# controllerver2.net
KiCad netlist of a schematic drawn in EAGLE
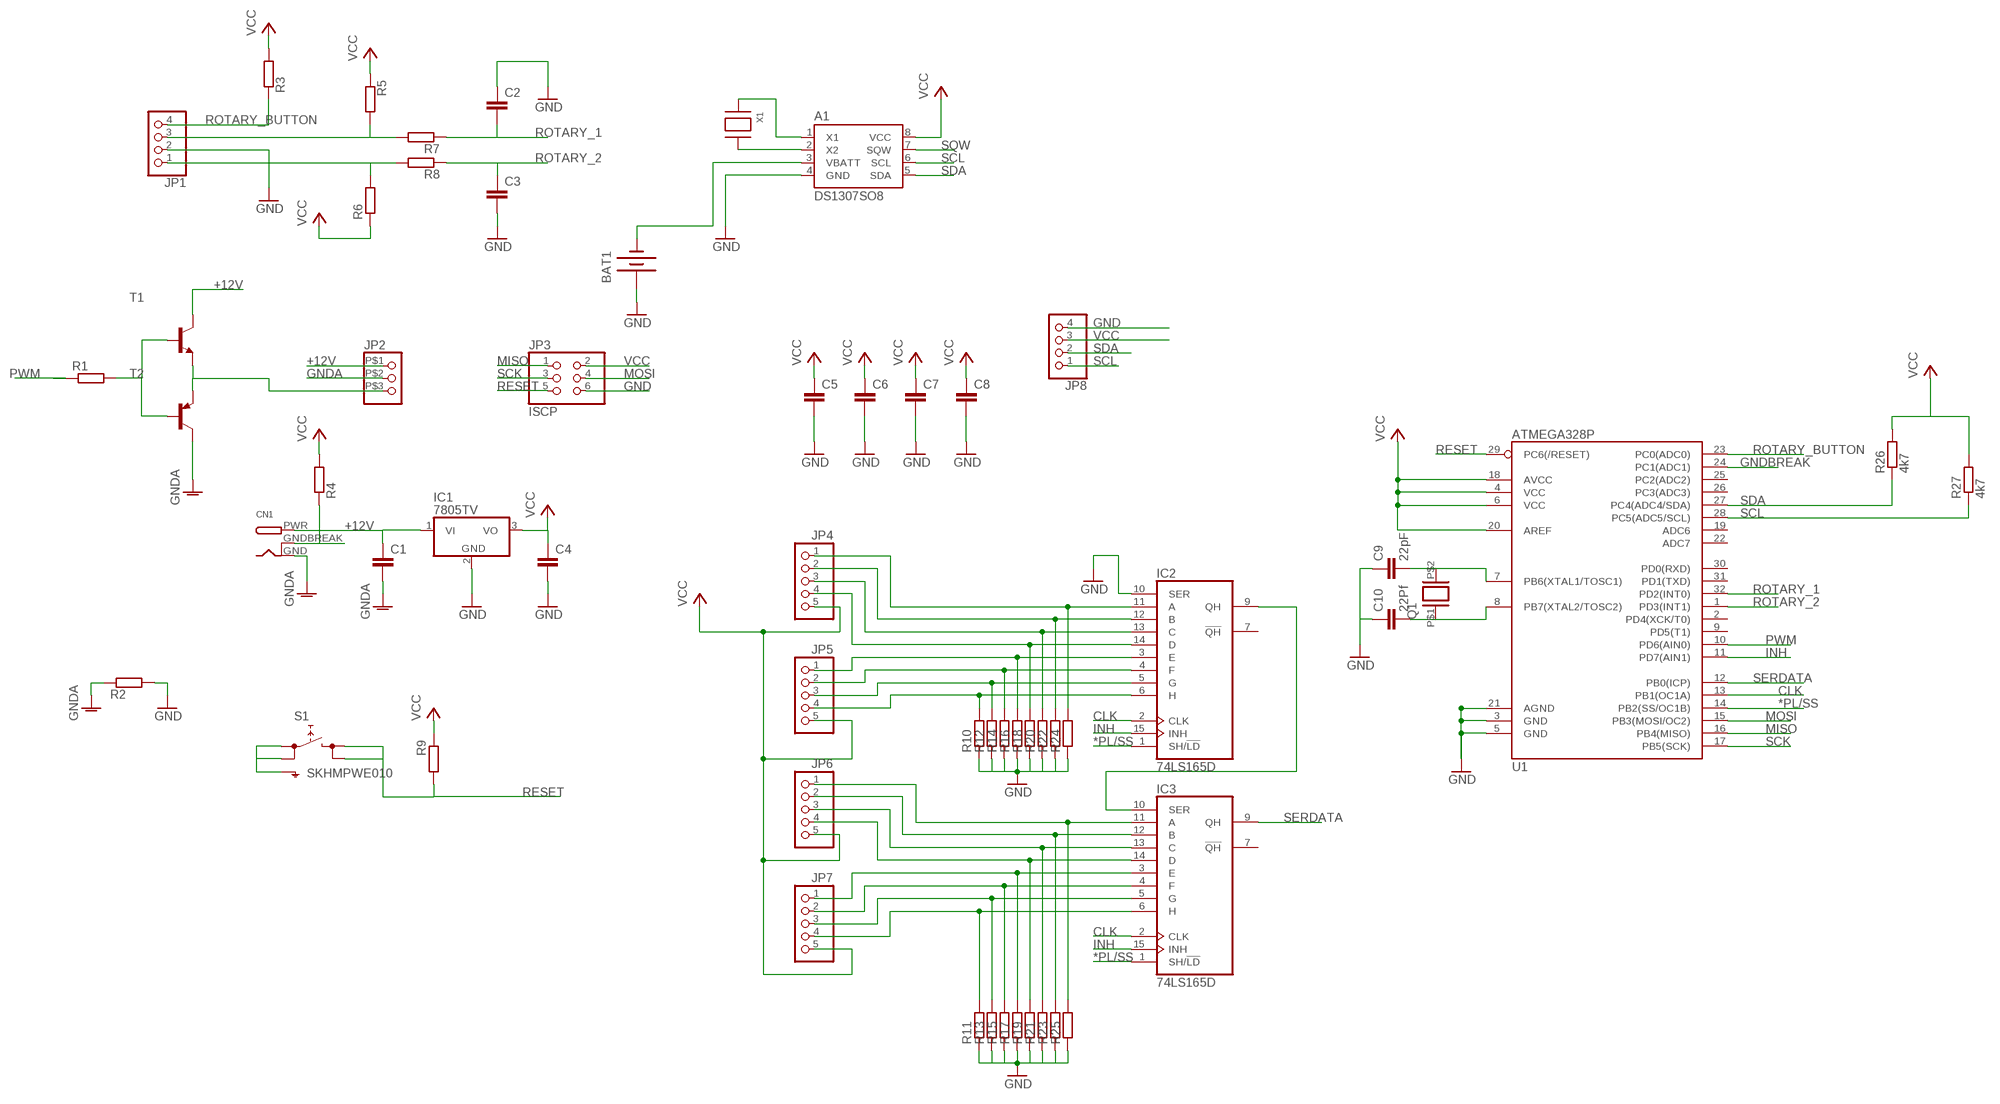
[diagram p0: schematic, sheet 1]

(export (version "E")
  (design (tool "Eeschema 10.0.6"))
  (components
    (comp (ref "A1")
      (value "DS1307SO8")
      (footprint "eagle-import:SO08")
      (libsource (lib "eagle-import") (part "DS1307SO8"))
    )
    (comp (ref "BAT1")
      (value "BATTERY20SMD")
      (footprint "eagle-import:BATTCON_20MM")
      (libsource (lib "eagle-import") (part "BATTERY20SMD"))
    )
    (comp (ref "C1")
      (value "C-EUC0805")
      (footprint "eagle-import:C0805")
      (libsource (lib "eagle-import") (part "C-EUC0805"))
    )
    (comp (ref "C2")
      (value "C-EUC0805")
      (footprint "eagle-import:C0805")
      (libsource (lib "eagle-import") (part "C-EUC0805"))
    )
    (comp (ref "C3")
      (value "C-EUC0805")
      (footprint "eagle-import:C0805")
      (libsource (lib "eagle-import") (part "C-EUC0805"))
    )
    (comp (ref "C4")
      (value "C-EUC0805")
      (footprint "eagle-import:C0805")
      (libsource (lib "eagle-import") (part "C-EUC0805"))
    )
    (comp (ref "C5")
      (value "C-EUC0805")
      (footprint "eagle-import:C0805")
      (libsource (lib "eagle-import") (part "C-EUC0805"))
    )
    (comp (ref "C6")
      (value "C-EUC0805")
      (footprint "eagle-import:C0805")
      (libsource (lib "eagle-import") (part "C-EUC0805"))
    )
    (comp (ref "C7")
      (value "C-EUC0805")
      (footprint "eagle-import:C0805")
      (libsource (lib "eagle-import") (part "C-EUC0805"))
    )
    (comp (ref "C8")
      (value "C-EUC0805")
      (footprint "eagle-import:C0805")
      (libsource (lib "eagle-import") (part "C-EUC0805"))
    )
    (comp (ref "C9")
      (value "22pF")
      (footprint "eagle-import:C0805")
      (libsource (lib "eagle-import") (part "C-EUC0805"))
    )
    (comp (ref "C10")
      (value "22Pf")
      (footprint "eagle-import:C0805")
      (libsource (lib "eagle-import") (part "C-EUC0805"))
    )
    (comp (ref "CN1")
      (value "DCBARRELPTH")
      (footprint "eagle-import:DCJACK_2MM_PTH")
      (libsource (lib "eagle-import") (part "DCBARRELPTH"))
    )
    (comp (ref "IC1")
      (value "7805TV")
      (footprint "eagle-import:TO220V")
      (libsource (lib "eagle-import") (part "78TV05"))
    )
    (comp (ref "IC2")
      (value "74LS165D")
      (footprint "eagle-import:SO16")
      (libsource (lib "eagle-import") (part "74165DLS"))
    )
    (comp (ref "IC3")
      (value "74LS165D")
      (footprint "eagle-import:SO16")
      (libsource (lib "eagle-import") (part "74165DLS"))
    )
    (comp (ref "JP1")
      (value "PINHD-1X4")
      (footprint "eagle-import:1X04")
      (libsource (lib "eagle-import") (part "PINHD-1X4"))
    )
    (comp (ref "JP2")
      (value "PINHD-1X35.08")
      (footprint "eagle-import:1X03_5.08")
      (libsource (lib "eagle-import") (part "PINHD-1X35.08"))
    )
    (comp (ref "JP3")
      (value "ISCP")
      (footprint "eagle-import:2X03")
      (libsource (lib "eagle-import") (part "PINHD-2X3"))
    )
    (comp (ref "JP4")
      (value "PINHD-1X5")
      (footprint "eagle-import:1X05")
      (libsource (lib "eagle-import") (part "PINHD-1X5"))
    )
    (comp (ref "JP5")
      (value "PINHD-1X5")
      (footprint "eagle-import:1X05")
      (libsource (lib "eagle-import") (part "PINHD-1X5"))
    )
    (comp (ref "JP6")
      (value "PINHD-1X5")
      (footprint "eagle-import:1X05")
      (libsource (lib "eagle-import") (part "PINHD-1X5"))
    )
    (comp (ref "JP7")
      (value "PINHD-1X5")
      (footprint "eagle-import:1X05")
      (libsource (lib "eagle-import") (part "PINHD-1X5"))
    )
    (comp (ref "JP8")
      (value "PINHD-1X4")
      (footprint "eagle-import:1X04")
      (libsource (lib "eagle-import") (part "PINHD-1X4"))
    )
    (comp (ref "Q1")
      (value "XTAL")
      (footprint "eagle-import:CSM-3X")
      (libsource (lib "eagle-import") (part "XTAL"))
    )
    (comp (ref "R1")
      (value "R-EU_R0805")
      (footprint "eagle-import:R0805")
      (libsource (lib "eagle-import") (part "R-EU_R0805"))
    )
    (comp (ref "R2")
      (value "R-EU_R0805")
      (footprint "eagle-import:R0805")
      (libsource (lib "eagle-import") (part "R-EU_R0805"))
    )
    (comp (ref "R3")
      (value "R-EU_R0805")
      (footprint "eagle-import:R0805")
      (libsource (lib "eagle-import") (part "R-EU_R0805"))
    )
    (comp (ref "R4")
      (value "R-EU_R0805")
      (footprint "eagle-import:R0805")
      (libsource (lib "eagle-import") (part "R-EU_R0805"))
    )
    (comp (ref "R5")
      (value "R-EU_R0805")
      (footprint "eagle-import:R0805")
      (libsource (lib "eagle-import") (part "R-EU_R0805"))
    )
    (comp (ref "R6")
      (value "R-EU_R0805")
      (footprint "eagle-import:R0805")
      (libsource (lib "eagle-import") (part "R-EU_R0805"))
    )
    (comp (ref "R7")
      (value "R-EU_R0805")
      (footprint "eagle-import:R0805")
      (libsource (lib "eagle-import") (part "R-EU_R0805"))
    )
    (comp (ref "R8")
      (value "R-EU_R0805")
      (footprint "eagle-import:R0805")
      (libsource (lib "eagle-import") (part "R-EU_R0805"))
    )
    (comp (ref "R9")
      (value "R-EU_R0805")
      (footprint "eagle-import:R0805")
      (libsource (lib "eagle-import") (part "R-EU_R0805"))
    )
    (comp (ref "R10")
      (value "R-EU_R0805")
      (footprint "eagle-import:R0805")
      (libsource (lib "eagle-import") (part "R-EU_R0805"))
    )
    (comp (ref "R11")
      (value "R-EU_R0805")
      (footprint "eagle-import:R0805")
      (libsource (lib "eagle-import") (part "R-EU_R0805"))
    )
    (comp (ref "R12")
      (value "R-EU_R0805")
      (footprint "eagle-import:R0805")
      (libsource (lib "eagle-import") (part "R-EU_R0805"))
    )
    (comp (ref "R13")
      (value "R-EU_R0805")
      (footprint "eagle-import:R0805")
      (libsource (lib "eagle-import") (part "R-EU_R0805"))
    )
    (comp (ref "R14")
      (value "R-EU_R0805")
      (footprint "eagle-import:R0805")
      (libsource (lib "eagle-import") (part "R-EU_R0805"))
    )
    (comp (ref "R15")
      (value "R-EU_R0805")
      (footprint "eagle-import:R0805")
      (libsource (lib "eagle-import") (part "R-EU_R0805"))
    )
    (comp (ref "R16")
      (value "R-EU_R0805")
      (footprint "eagle-import:R0805")
      (libsource (lib "eagle-import") (part "R-EU_R0805"))
    )
    (comp (ref "R17")
      (value "R-EU_R0805")
      (footprint "eagle-import:R0805")
      (libsource (lib "eagle-import") (part "R-EU_R0805"))
    )
    (comp (ref "R18")
      (value "R-EU_R0805")
      (footprint "eagle-import:R0805")
      (libsource (lib "eagle-import") (part "R-EU_R0805"))
    )
    (comp (ref "R19")
      (value "R-EU_R0805")
      (footprint "eagle-import:R0805")
      (libsource (lib "eagle-import") (part "R-EU_R0805"))
    )
    (comp (ref "R20")
      (value "R-EU_R0805")
      (footprint "eagle-import:R0805")
      (libsource (lib "eagle-import") (part "R-EU_R0805"))
    )
    (comp (ref "R21")
      (value "R-EU_R0805")
      (footprint "eagle-import:R0805")
      (libsource (lib "eagle-import") (part "R-EU_R0805"))
    )
    (comp (ref "R22")
      (value "R-EU_R0805")
      (footprint "eagle-import:R0805")
      (libsource (lib "eagle-import") (part "R-EU_R0805"))
    )
    (comp (ref "R23")
      (value "R-EU_R0805")
      (footprint "eagle-import:R0805")
      (libsource (lib "eagle-import") (part "R-EU_R0805"))
    )
    (comp (ref "R24")
      (value "R-EU_R0805")
      (footprint "eagle-import:R0805")
      (libsource (lib "eagle-import") (part "R-EU_R0805"))
    )
    (comp (ref "R25")
      (value "R-EU_R0805")
      (footprint "eagle-import:R0805")
      (libsource (lib "eagle-import") (part "R-EU_R0805"))
    )
    (comp (ref "R26")
      (value "4k7")
      (footprint "eagle-import:R0805")
      (libsource (lib "eagle-import") (part "R-EU_R0805"))
    )
    (comp (ref "R27")
      (value "4k7")
      (footprint "eagle-import:R0805")
      (libsource (lib "eagle-import") (part "R-EU_R0805"))
    )
    (comp (ref "S1")
      (value "SKHMPWE010")
      (footprint "eagle-import:SKHMPXE010")
      (libsource (lib "eagle-import") (part "SKHMPE010W"))
    )
    (comp (ref "T1")
      (value "BC847-NPN-SOT23-BEC")
      (footprint "eagle-import:SOT23-BEC")
      (libsource (lib "eagle-import") (part "-NPN-SOT23-BECBC847"))
    )
    (comp (ref "T2")
      (value "BC807-16-PNP-SOT23-BEC")
      (footprint "eagle-import:SOT23-BEC")
      (libsource (lib "eagle-import") (part "-PNP-SOT23-BECBC807-16"))
    )
    (comp (ref "U1")
      (value "ATMEGA328P")
      (footprint "eagle-import:TQFP32-08")
      (libsource (lib "eagle-import") (part "ATMEGA328_SMT"))
    )
    (comp (ref "X1")
      (value "XTAL-3.2X1.5")
      (footprint "eagle-import:XTAL3215")
      (libsource (lib "eagle-import") (part "XTAL-3.2X1.5"))
    )
  )
  (nets
    (net (code "1") (name "/*PL{slash}SS") (class "Default")
      (node (ref "IC2") (pin "1") (pinfunction "SH/~{LD}_1") (pintype "input"))
      (node (ref "IC3") (pin "1") (pinfunction "SH/~{LD}_1") (pintype "input"))
      (node (ref "U1") (pin "14") (pinfunction "PB2(SS/OC1B)_14") (pintype "bidirectional"))
    )
    (net (code "2") (name "/+12V") (class "Default")
      (node (ref "C1") (pin "1") (pinfunction "1_1") (pintype "passive"))
      (node (ref "CN1") (pin "PWR") (pinfunction "PWR_PWR") (pintype "power_in"))
      (node (ref "IC1") (pin "1") (pinfunction "VI_1") (pintype "input"))
      (node (ref "JP2") (pin "P$1") (pinfunction "1_P$1") (pintype "passive"))
      (node (ref "T1") (pin "C") (pinfunction "C_C") (pintype "passive"))
    )
    (net (code "3") (name "/CLK") (class "Default")
      (node (ref "IC2") (pin "2") (pinfunction "CLK_2") (pintype "input"))
      (node (ref "IC3") (pin "2") (pinfunction "CLK_2") (pintype "input"))
      (node (ref "U1") (pin "13") (pinfunction "PB1(OC1A)_13") (pintype "bidirectional"))
    )
    (net (code "4") (name "/GNDBREAK") (class "Default")
      (node (ref "CN1") (pin "GNDBREAK") (pinfunction "GNDBREAK_GNDBREAK") (pintype "power_in"))
      (node (ref "R4") (pin "1") (pinfunction "1_1") (pintype "passive"))
      (node (ref "U1") (pin "24") (pinfunction "PC1(ADC1)_24") (pintype "bidirectional"))
    )
    (net (code "5") (name "/INH") (class "Default")
      (node (ref "IC2") (pin "15") (pinfunction "INH_15") (pintype "input"))
      (node (ref "IC3") (pin "15") (pinfunction "INH_15") (pintype "input"))
      (node (ref "U1") (pin "11") (pinfunction "PD7(AIN1)_11") (pintype "bidirectional"))
    )
    (net (code "6") (name "/MISO") (class "Default")
      (node (ref "JP3") (pin "1") (pinfunction "1_1") (pintype "passive"))
      (node (ref "U1") (pin "16") (pinfunction "PB4(MISO)_16") (pintype "bidirectional"))
    )
    (net (code "7") (name "/MOSI") (class "Default")
      (node (ref "JP3") (pin "4") (pinfunction "4_4") (pintype "passive"))
      (node (ref "U1") (pin "15") (pinfunction "PB3(MOSI/OC2)_15") (pintype "bidirectional"))
    )
    (net (code "8") (name "/PWM") (class "Default")
      (node (ref "R1") (pin "1") (pinfunction "1_1") (pintype "passive"))
      (node (ref "U1") (pin "10") (pinfunction "PD6(AIN0)_10") (pintype "bidirectional"))
    )
    (net (code "9") (name "/RESET") (class "Default")
      (node (ref "JP3") (pin "5") (pinfunction "5_5") (pintype "passive"))
      (node (ref "R9") (pin "2") (pinfunction "2_2") (pintype "passive"))
      (node (ref "S1") (pin "3") (pinfunction "2.1_3") (pintype "passive"))
      (node (ref "S1") (pin "4") (pinfunction "2.2_4") (pintype "passive"))
      (node (ref "U1") (pin "29") (pinfunction "PC6(/RESET)_29") (pintype "bidirectional"))
    )
    (net (code "10") (name "/ROTARY_1") (class "Default")
      (node (ref "C2") (pin "2") (pinfunction "2_2") (pintype "passive"))
      (node (ref "R7") (pin "1") (pinfunction "1_1") (pintype "passive"))
      (node (ref "U1") (pin "32") (pinfunction "PD2(INT0)_32") (pintype "bidirectional"))
    )
    (net (code "11") (name "/ROTARY_2") (class "Default")
      (node (ref "C3") (pin "1") (pinfunction "1_1") (pintype "passive"))
      (node (ref "R8") (pin "1") (pinfunction "1_1") (pintype "passive"))
      (node (ref "U1") (pin "1") (pinfunction "PD3(INT1)_1") (pintype "bidirectional"))
    )
    (net (code "12") (name "/ROTARY_BUTTON") (class "Default")
      (node (ref "JP1") (pin "4") (pinfunction "4_4") (pintype "passive"))
      (node (ref "R3") (pin "1") (pinfunction "1_1") (pintype "passive"))
      (node (ref "U1") (pin "23") (pinfunction "PC0(ADC0)_23") (pintype "bidirectional"))
    )
    (net (code "13") (name "/SCK") (class "Default")
      (node (ref "JP3") (pin "3") (pinfunction "3_3") (pintype "passive"))
      (node (ref "U1") (pin "17") (pinfunction "PB5(SCK)_17") (pintype "bidirectional"))
    )
    (net (code "14") (name "/SCL") (class "Default")
      (node (ref "A1") (pin "6") (pinfunction "SCL_6") (pintype "bidirectional"))
      (node (ref "JP8") (pin "1") (pinfunction "1_1") (pintype "passive"))
      (node (ref "R27") (pin "1") (pinfunction "1_1") (pintype "passive"))
      (node (ref "U1") (pin "28") (pinfunction "PC5(ADC5/SCL)_28") (pintype "bidirectional"))
    )
    (net (code "15") (name "/SDA") (class "Default")
      (node (ref "A1") (pin "5") (pinfunction "SDA_5") (pintype "bidirectional"))
      (node (ref "JP8") (pin "2") (pinfunction "2_2") (pintype "passive"))
      (node (ref "R26") (pin "1") (pinfunction "1_1") (pintype "passive"))
      (node (ref "U1") (pin "27") (pinfunction "PC4(ADC4/SDA)_27") (pintype "bidirectional"))
    )
    (net (code "16") (name "/SERDATA") (class "Default")
      (node (ref "IC3") (pin "9") (pinfunction "QH_9") (pintype "output"))
      (node (ref "U1") (pin "12") (pinfunction "PB0(ICP)_12") (pintype "bidirectional"))
    )
    (net (code "17") (name "/SQW") (class "Default")
      (node (ref "A1") (pin "7") (pinfunction "SQW_7") (pintype "bidirectional"))
    )
    (net (code "18") (name "GND") (class "Default")
      (node (ref "A1") (pin "4") (pinfunction "GND_4") (pintype "bidirectional"))
      (node (ref "BAT1") (pin "1") (pinfunction "+_1") (pintype "power_in"))
      (node (ref "C10") (pin "1") (pinfunction "1_1") (pintype "passive"))
      (node (ref "C2") (pin "1") (pinfunction "1_1") (pintype "passive"))
      (node (ref "C3") (pin "2") (pinfunction "2_2") (pintype "passive"))
      (node (ref "C4") (pin "2") (pinfunction "2_2") (pintype "passive"))
      (node (ref "C5") (pin "2") (pinfunction "2_2") (pintype "passive"))
      (node (ref "C6") (pin "2") (pinfunction "2_2") (pintype "passive"))
      (node (ref "C7") (pin "2") (pinfunction "2_2") (pintype "passive"))
      (node (ref "C8") (pin "2") (pinfunction "2_2") (pintype "passive"))
      (node (ref "C9") (pin "1") (pinfunction "1_1") (pintype "passive"))
      (node (ref "IC1") (pin "2") (pinfunction "GND_2") (pintype "passive"))
      (node (ref "IC2") (pin "10") (pinfunction "SER_10") (pintype "input"))
      (node (ref "JP1") (pin "2") (pinfunction "2_2") (pintype "passive"))
      (node (ref "JP3") (pin "6") (pinfunction "6_6") (pintype "passive"))
      (node (ref "JP8") (pin "4") (pinfunction "4_4") (pintype "passive"))
      (node (ref "R10") (pin "1") (pinfunction "1_1") (pintype "passive"))
      (node (ref "R11") (pin "1") (pinfunction "1_1") (pintype "passive"))
      (node (ref "R12") (pin "1") (pinfunction "1_1") (pintype "passive"))
      (node (ref "R13") (pin "1") (pinfunction "1_1") (pintype "passive"))
      (node (ref "R14") (pin "1") (pinfunction "1_1") (pintype "passive"))
      (node (ref "R15") (pin "1") (pinfunction "1_1") (pintype "passive"))
      (node (ref "R16") (pin "1") (pinfunction "1_1") (pintype "passive"))
      (node (ref "R17") (pin "1") (pinfunction "1_1") (pintype "passive"))
      (node (ref "R18") (pin "1") (pinfunction "1_1") (pintype "passive"))
      (node (ref "R19") (pin "1") (pinfunction "1_1") (pintype "passive"))
      (node (ref "R2") (pin "2") (pinfunction "2_2") (pintype "passive"))
      (node (ref "R20") (pin "1") (pinfunction "1_1") (pintype "passive"))
      (node (ref "R21") (pin "1") (pinfunction "1_1") (pintype "passive"))
      (node (ref "R22") (pin "1") (pinfunction "1_1") (pintype "passive"))
      (node (ref "R23") (pin "1") (pinfunction "1_1") (pintype "passive"))
      (node (ref "R24") (pin "1") (pinfunction "1_1") (pintype "passive"))
      (node (ref "R25") (pin "1") (pinfunction "1_1") (pintype "passive"))
      (node (ref "S1") (pin "1") (pinfunction "1.1_1") (pintype "passive"))
      (node (ref "S1") (pin "2") (pinfunction "1.2_2") (pintype "passive"))
      (node (ref "S1") (pin "5") (pinfunction "SH_5") (pintype "passive"))
      (node (ref "U1") (pin "21") (pinfunction "AGND_21") (pintype "bidirectional"))
      (node (ref "U1") (pin "3") (pinfunction "GND_3") (pintype "bidirectional"))
      (node (ref "U1") (pin "5") (pinfunction "GND_5") (pintype "bidirectional"))
    )
    (net (code "19") (name "GNDA") (class "Default")
      (node (ref "C1") (pin "2") (pinfunction "2_2") (pintype "passive"))
      (node (ref "CN1") (pin "GND") (pinfunction "GND_GND") (pintype "power_in"))
      (node (ref "JP2") (pin "P$2") (pinfunction "2_P$2") (pintype "passive"))
      (node (ref "R2") (pin "1") (pinfunction "1_1") (pintype "passive"))
      (node (ref "T2") (pin "C") (pinfunction "C_C") (pintype "passive"))
    )
    (net (code "20") (name "Net-(A1-VBATT)") (class "Default")
      (node (ref "A1") (pin "3") (pinfunction "VBATT_3") (pintype "bidirectional"))
      (node (ref "BAT1") (pin "2") (pinfunction "-_2") (pintype "power_in"))
    )
    (net (code "21") (name "Net-(A1-X1)") (class "Default")
      (node (ref "A1") (pin "1") (pinfunction "X1_1") (pintype "bidirectional"))
      (node (ref "X1") (pin "P$1") (pinfunction "P$1_P$1") (pintype "bidirectional"))
    )
    (net (code "22") (name "Net-(A1-X2)") (class "Default")
      (node (ref "A1") (pin "2") (pinfunction "X2_2") (pintype "bidirectional"))
      (node (ref "X1") (pin "P$2") (pinfunction "P$2_P$2") (pintype "bidirectional"))
    )
    (net (code "23") (name "Net-(IC2A-A)") (class "Default")
      (node (ref "IC2") (pin "11") (pinfunction "A_11") (pintype "input"))
      (node (ref "JP4") (pin "1") (pinfunction "1_1") (pintype "passive"))
      (node (ref "R24") (pin "2") (pinfunction "2_2") (pintype "passive"))
    )
    (net (code "24") (name "Net-(IC2A-B)") (class "Default")
      (node (ref "IC2") (pin "12") (pinfunction "B_12") (pintype "input"))
      (node (ref "JP4") (pin "2") (pinfunction "2_2") (pintype "passive"))
      (node (ref "R22") (pin "2") (pinfunction "2_2") (pintype "passive"))
    )
    (net (code "25") (name "Net-(IC2A-C)") (class "Default")
      (node (ref "IC2") (pin "13") (pinfunction "C_13") (pintype "input"))
      (node (ref "JP4") (pin "3") (pinfunction "3_3") (pintype "passive"))
      (node (ref "R20") (pin "2") (pinfunction "2_2") (pintype "passive"))
    )
    (net (code "26") (name "Net-(IC2A-D)") (class "Default")
      (node (ref "IC2") (pin "14") (pinfunction "D_14") (pintype "input"))
      (node (ref "JP4") (pin "4") (pinfunction "4_4") (pintype "passive"))
      (node (ref "R18") (pin "2") (pinfunction "2_2") (pintype "passive"))
    )
    (net (code "27") (name "Net-(IC2A-E)") (class "Default")
      (node (ref "IC2") (pin "3") (pinfunction "E_3") (pintype "input"))
      (node (ref "JP5") (pin "1") (pinfunction "1_1") (pintype "passive"))
      (node (ref "R16") (pin "2") (pinfunction "2_2") (pintype "passive"))
    )
    (net (code "28") (name "Net-(IC2A-F)") (class "Default")
      (node (ref "IC2") (pin "4") (pinfunction "F_4") (pintype "input"))
      (node (ref "JP5") (pin "2") (pinfunction "2_2") (pintype "passive"))
      (node (ref "R14") (pin "2") (pinfunction "2_2") (pintype "passive"))
    )
    (net (code "29") (name "Net-(IC2A-G)") (class "Default")
      (node (ref "IC2") (pin "5") (pinfunction "G_5") (pintype "input"))
      (node (ref "JP5") (pin "3") (pinfunction "3_3") (pintype "passive"))
      (node (ref "R12") (pin "2") (pinfunction "2_2") (pintype "passive"))
    )
    (net (code "30") (name "Net-(IC2A-H)") (class "Default")
      (node (ref "IC2") (pin "6") (pinfunction "H_6") (pintype "input"))
      (node (ref "JP5") (pin "4") (pinfunction "4_4") (pintype "passive"))
      (node (ref "R10") (pin "2") (pinfunction "2_2") (pintype "passive"))
    )
    (net (code "31") (name "Net-(IC2A-QH)") (class "Default")
      (node (ref "IC2") (pin "9") (pinfunction "QH_9") (pintype "output"))
      (node (ref "IC3") (pin "10") (pinfunction "SER_10") (pintype "input"))
    )
    (net (code "32") (name "Net-(IC3A-A)") (class "Default")
      (node (ref "IC3") (pin "11") (pinfunction "A_11") (pintype "input"))
      (node (ref "JP6") (pin "1") (pinfunction "1_1") (pintype "passive"))
      (node (ref "R25") (pin "2") (pinfunction "2_2") (pintype "passive"))
    )
    (net (code "33") (name "Net-(IC3A-B)") (class "Default")
      (node (ref "IC3") (pin "12") (pinfunction "B_12") (pintype "input"))
      (node (ref "JP6") (pin "2") (pinfunction "2_2") (pintype "passive"))
      (node (ref "R23") (pin "2") (pinfunction "2_2") (pintype "passive"))
    )
    (net (code "34") (name "Net-(IC3A-C)") (class "Default")
      (node (ref "IC3") (pin "13") (pinfunction "C_13") (pintype "input"))
      (node (ref "JP6") (pin "3") (pinfunction "3_3") (pintype "passive"))
      (node (ref "R21") (pin "2") (pinfunction "2_2") (pintype "passive"))
    )
    (net (code "35") (name "Net-(IC3A-D)") (class "Default")
      (node (ref "IC3") (pin "14") (pinfunction "D_14") (pintype "input"))
      (node (ref "JP6") (pin "4") (pinfunction "4_4") (pintype "passive"))
      (node (ref "R19") (pin "2") (pinfunction "2_2") (pintype "passive"))
    )
    (net (code "36") (name "Net-(IC3A-E)") (class "Default")
      (node (ref "IC3") (pin "3") (pinfunction "E_3") (pintype "input"))
      (node (ref "JP7") (pin "1") (pinfunction "1_1") (pintype "passive"))
      (node (ref "R17") (pin "2") (pinfunction "2_2") (pintype "passive"))
    )
    (net (code "37") (name "Net-(IC3A-F)") (class "Default")
      (node (ref "IC3") (pin "4") (pinfunction "F_4") (pintype "input"))
      (node (ref "JP7") (pin "2") (pinfunction "2_2") (pintype "passive"))
      (node (ref "R15") (pin "2") (pinfunction "2_2") (pintype "passive"))
    )
    (net (code "38") (name "Net-(IC3A-G)") (class "Default")
      (node (ref "IC3") (pin "5") (pinfunction "G_5") (pintype "input"))
      (node (ref "JP7") (pin "3") (pinfunction "3_3") (pintype "passive"))
      (node (ref "R13") (pin "2") (pinfunction "2_2") (pintype "passive"))
    )
    (net (code "39") (name "Net-(IC3A-H)") (class "Default")
      (node (ref "IC3") (pin "6") (pinfunction "H_6") (pintype "input"))
      (node (ref "JP7") (pin "4") (pinfunction "4_4") (pintype "passive"))
      (node (ref "R11") (pin "2") (pinfunction "2_2") (pintype "passive"))
    )
    (net (code "40") (name "Net-(JP1-Pad1)") (class "Default")
      (node (ref "JP1") (pin "1") (pinfunction "1_1") (pintype "passive"))
      (node (ref "R6") (pin "2") (pinfunction "2_2") (pintype "passive"))
      (node (ref "R8") (pin "2") (pinfunction "2_2") (pintype "passive"))
    )
    (net (code "41") (name "Net-(JP1-Pad3)") (class "Default")
      (node (ref "JP1") (pin "3") (pinfunction "3_3") (pintype "passive"))
      (node (ref "R5") (pin "2") (pinfunction "2_2") (pintype "passive"))
      (node (ref "R7") (pin "2") (pinfunction "2_2") (pintype "passive"))
    )
    (net (code "42") (name "Net-(JP2-3)") (class "Default")
      (node (ref "JP2") (pin "P$3") (pinfunction "3_P$3") (pintype "passive"))
      (node (ref "T1") (pin "E") (pinfunction "E_E") (pintype "passive"))
      (node (ref "T2") (pin "E") (pinfunction "E_E") (pintype "passive"))
    )
    (net (code "43") (name "Net-(Q1-1)") (class "Default")
      (node (ref "C10") (pin "2") (pinfunction "2_2") (pintype "passive"))
      (node (ref "Q1") (pin "P$1") (pinfunction "1_P$1") (pintype "passive"))
      (node (ref "U1") (pin "8") (pinfunction "PB7(XTAL2/TOSC2)_8") (pintype "bidirectional"))
    )
    (net (code "44") (name "Net-(Q1-2)") (class "Default")
      (node (ref "C9") (pin "2") (pinfunction "2_2") (pintype "passive"))
      (node (ref "Q1") (pin "P$2") (pinfunction "2_P$2") (pintype "passive"))
      (node (ref "U1") (pin "7") (pinfunction "PB6(XTAL1/TOSC1)_7") (pintype "bidirectional"))
    )
    (net (code "45") (name "Net-(R1-Pad2)") (class "Default")
      (node (ref "R1") (pin "2") (pinfunction "2_2") (pintype "passive"))
      (node (ref "T1") (pin "B") (pinfunction "B_B") (pintype "passive"))
      (node (ref "T2") (pin "B") (pinfunction "B_B") (pintype "passive"))
    )
    (net (code "46") (name "VCC") (class "Default")
      (node (ref "A1") (pin "8") (pinfunction "VCC_8") (pintype "bidirectional"))
      (node (ref "C4") (pin "1") (pinfunction "1_1") (pintype "passive"))
      (node (ref "C5") (pin "1") (pinfunction "1_1") (pintype "passive"))
      (node (ref "C6") (pin "1") (pinfunction "1_1") (pintype "passive"))
      (node (ref "C7") (pin "1") (pinfunction "1_1") (pintype "passive"))
      (node (ref "C8") (pin "1") (pinfunction "1_1") (pintype "passive"))
      (node (ref "IC1") (pin "3") (pinfunction "VO_3") (pintype "passive"))
      (node (ref "JP3") (pin "2") (pinfunction "2_2") (pintype "passive"))
      (node (ref "JP4") (pin "5") (pinfunction "5_5") (pintype "passive"))
      (node (ref "JP5") (pin "5") (pinfunction "5_5") (pintype "passive"))
      (node (ref "JP6") (pin "5") (pinfunction "5_5") (pintype "passive"))
      (node (ref "JP7") (pin "5") (pinfunction "5_5") (pintype "passive"))
      (node (ref "JP8") (pin "3") (pinfunction "3_3") (pintype "passive"))
      (node (ref "R26") (pin "2") (pinfunction "2_2") (pintype "passive"))
      (node (ref "R27") (pin "2") (pinfunction "2_2") (pintype "passive"))
      (node (ref "R3") (pin "2") (pinfunction "2_2") (pintype "passive"))
      (node (ref "R4") (pin "2") (pinfunction "2_2") (pintype "passive"))
      (node (ref "R5") (pin "1") (pinfunction "1_1") (pintype "passive"))
      (node (ref "R6") (pin "1") (pinfunction "1_1") (pintype "passive"))
      (node (ref "R9") (pin "1") (pinfunction "1_1") (pintype "passive"))
      (node (ref "U1") (pin "18") (pinfunction "AVCC_18") (pintype "bidirectional"))
      (node (ref "U1") (pin "20") (pinfunction "AREF_20") (pintype "bidirectional"))
      (node (ref "U1") (pin "4") (pinfunction "VCC_4") (pintype "bidirectional"))
      (node (ref "U1") (pin "6") (pinfunction "VCC_6") (pintype "bidirectional"))
    )
    (net (code "47") (name "unconnected-(IC2A-~{QH}-Pad7)") (class "Default")
      (node (ref "IC2") (pin "7") (pinfunction "~{QH}_7") (pintype "output"))
    )
    (net (code "48") (name "unconnected-(IC3A-~{QH}-Pad7)") (class "Default")
      (node (ref "IC3") (pin "7") (pinfunction "~{QH}_7") (pintype "output"))
    )
    (net (code "49") (name "unconnected-(U1-ADC6-Pad19)") (class "Default")
      (node (ref "U1") (pin "19") (pinfunction "ADC6_19") (pintype "bidirectional"))
    )
    (net (code "50") (name "unconnected-(U1-ADC7-Pad22)") (class "Default")
      (node (ref "U1") (pin "22") (pinfunction "ADC7_22") (pintype "bidirectional"))
    )
    (net (code "51") (name "unconnected-(U1-PC2(ADC2)-Pad25)") (class "Default")
      (node (ref "U1") (pin "25") (pinfunction "PC2(ADC2)_25") (pintype "bidirectional"))
    )
    (net (code "52") (name "unconnected-(U1-PC3(ADC3)-Pad26)") (class "Default")
      (node (ref "U1") (pin "26") (pinfunction "PC3(ADC3)_26") (pintype "bidirectional"))
    )
    (net (code "53") (name "unconnected-(U1-PD0(RXD)-Pad30)") (class "Default")
      (node (ref "U1") (pin "30") (pinfunction "PD0(RXD)_30") (pintype "bidirectional"))
    )
    (net (code "54") (name "unconnected-(U1-PD1(TXD)-Pad31)") (class "Default")
      (node (ref "U1") (pin "31") (pinfunction "PD1(TXD)_31") (pintype "bidirectional"))
    )
    (net (code "55") (name "unconnected-(U1-PD4(XCK{slash}T0)-Pad2)") (class "Default")
      (node (ref "U1") (pin "2") (pinfunction "PD4(XCK/T0)_2") (pintype "bidirectional"))
    )
    (net (code "56") (name "unconnected-(U1-PD5(T1)-Pad9)") (class "Default")
      (node (ref "U1") (pin "9") (pinfunction "PD5(T1)_9") (pintype "bidirectional"))
    )
  )
)
